# gsm_LoRa_due.net
KiCad netlist of a schematic drawn in EAGLE
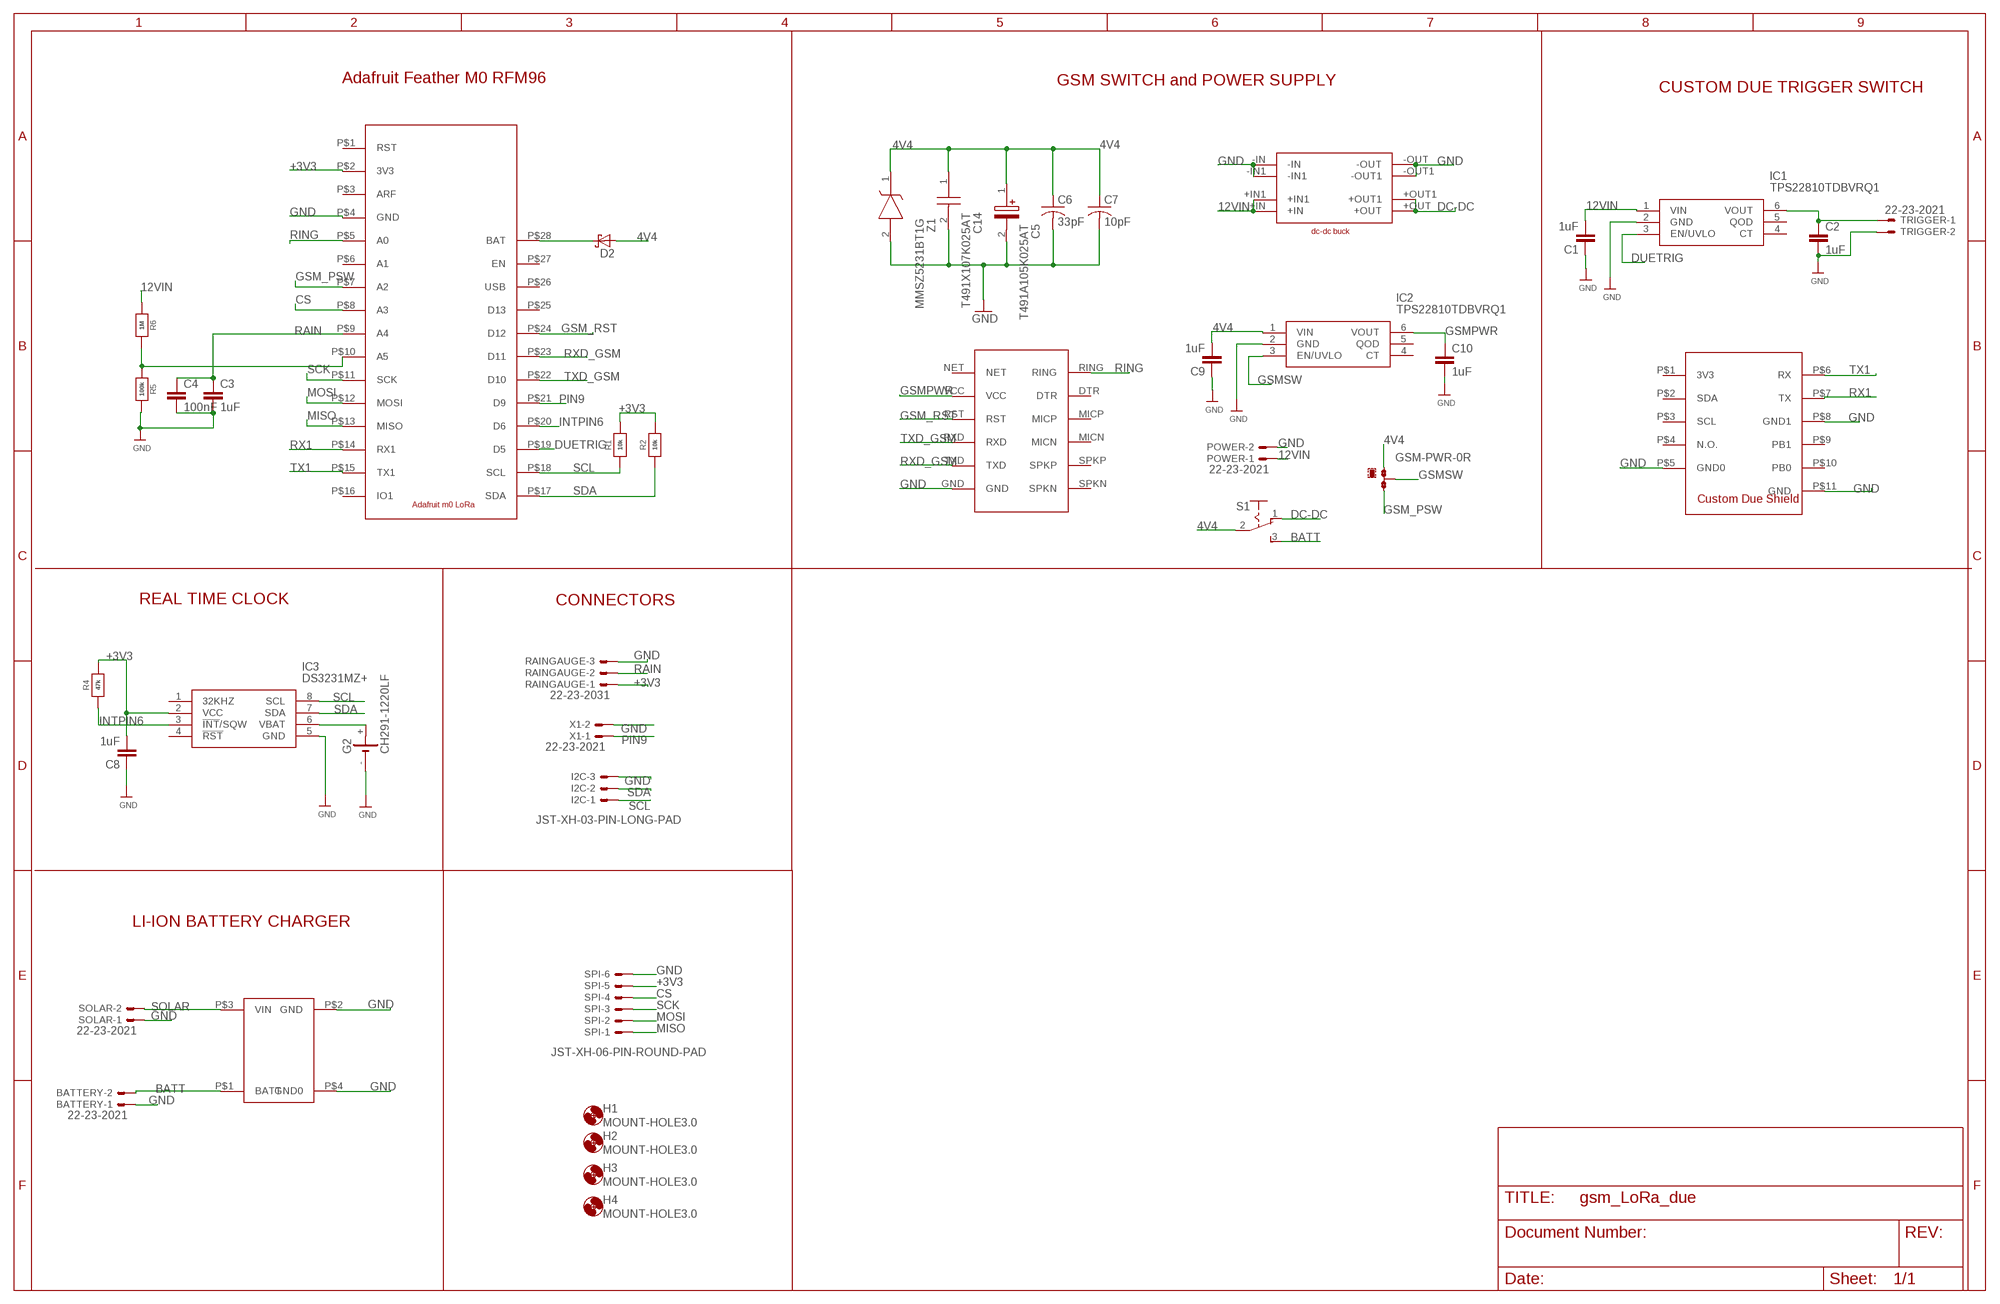
[diagram p0: schematic, sheet 1]

(export (version "E")
  (design (tool "Eeschema 10.0.6"))
  (components
    (comp (ref "BATTERY")
      (value "22-23-2021")
      (footprint "eagle-import:22-23-2021")
      (fields (field (name "MF") "MOLEX"))
      (libsource (lib "eagle-import") (part "22-23-2021"))
    )
    (comp (ref "C1")
      (value "1uF")
      (footprint "eagle-import:C0603")
      (libsource (lib "eagle-import") (part "CC0603"))
    )
    (comp (ref "C2")
      (value "1uF")
      (footprint "eagle-import:C0603")
      (libsource (lib "eagle-import") (part "CC0603"))
    )
    (comp (ref "C3")
      (value "1uF")
      (footprint "eagle-import:C0603")
      (libsource (lib "eagle-import") (part "CC0603"))
    )
    (comp (ref "C4")
      (value "100nF")
      (footprint "eagle-import:C0603")
      (libsource (lib "eagle-import") (part "CC0603"))
    )
    (comp (ref "C5")
      (value "T491A105K025AT")
      (footprint "eagle-import:CAPPM3216X180N")
      (fields (field (name "RS_PART_NUMBER") "8685769"))
      (libsource (lib "eagle-import") (part "T491A105K025AT"))
    )
    (comp (ref "C6")
      (value "33pF")
      (footprint "eagle-import:C0603")
      (libsource (lib "eagle-import") (part "C-USC0603"))
    )
    (comp (ref "C7")
      (value "10pF")
      (footprint "eagle-import:C0603")
      (libsource (lib "eagle-import") (part "C-USC0603"))
    )
    (comp (ref "C8")
      (value "1uF")
      (footprint "eagle-import:C0603")
      (libsource (lib "eagle-import") (part "CC0603"))
    )
    (comp (ref "C9")
      (value "1uF")
      (footprint "eagle-import:C0603")
      (libsource (lib "eagle-import") (part "CC0603"))
    )
    (comp (ref "C10")
      (value "1uF")
      (footprint "eagle-import:C0603")
      (libsource (lib "eagle-import") (part "CC0603"))
    )
    (comp (ref "C14")
      (value "T491X107K025AT")
      (footprint "eagle-import:CAPPM7343X430N")
      (fields (field (name "RS_PART_NUMBER") "8015511P"))
      (libsource (lib "eagle-import") (part "T491X107K025AT"))
    )
    (comp (ref "D2")
      (value "SCHOTTKY-DIODE")
      (footprint "eagle-import:DIODE_SMB")
      (libsource (lib "eagle-import") (part "SCHOTTKY-DIODE"))
    )
    (comp (ref "G2")
      (value "CH291-1220LF")
      (footprint "eagle-import:CH291-1220LF")
      (libsource (lib "eagle-import") (part "CH291-1220LF"))
    )
    (comp (ref "GSM-PWR")
      (value "0R-JUMPB")
      (footprint "eagle-import:B0R-JMP")
      (libsource (lib "eagle-import") (part "0R-JUMPB"))
    )
    (comp (ref "H1")
      (value "MOUNT-HOLE3.0")
      (footprint "eagle-import:3,0")
      (libsource (lib "eagle-import") (part "MOUNT-HOLE3.0"))
    )
    (comp (ref "H2")
      (value "MOUNT-HOLE3.0")
      (footprint "eagle-import:3,0")
      (libsource (lib "eagle-import") (part "MOUNT-HOLE3.0"))
    )
    (comp (ref "H3")
      (value "MOUNT-HOLE3.0")
      (footprint "eagle-import:3,0")
      (libsource (lib "eagle-import") (part "MOUNT-HOLE3.0"))
    )
    (comp (ref "H4")
      (value "MOUNT-HOLE3.0")
      (footprint "eagle-import:3,0")
      (libsource (lib "eagle-import") (part "MOUNT-HOLE3.0"))
    )
    (comp (ref "I2C")
      (value "JST-XH-03-PIN-LONG-PAD")
      (footprint "eagle-import:JST-XH-03-PACKAGE-LONG-PAD")
      (libsource (lib "eagle-import") (part "JST-XH-03-PIN-LONG-PAD"))
    )
    (comp (ref "IC1")
      (value "TPS22810TDBVRQ1")
      (footprint "eagle-import:SOT95P280X145-6N")
      (libsource (lib "eagle-import") (part "TPS22810TDBVRQ1"))
    )
    (comp (ref "IC2")
      (value "TPS22810TDBVRQ1")
      (footprint "eagle-import:SOT95P280X145-6N")
      (libsource (lib "eagle-import") (part "TPS22810TDBVRQ1"))
    )
    (comp (ref "IC3")
      (value "DS3231MZ+")
      (footprint "eagle-import:SOIC127P600X175-8N")
      (fields (field (name "RS_PART_NUMBER") "1897249"))
      (libsource (lib "eagle-import") (part "DS3231MZ+"))
    )
    (comp (ref "POWER")
      (value "22-23-2021")
      (footprint "eagle-import:22-23-2021")
      (fields (field (name "MF") "MOLEX"))
      (libsource (lib "eagle-import") (part "22-23-2021"))
    )
    (comp (ref "R1")
      (value "10k")
      (footprint "eagle-import:0603-NO")
      (libsource (lib "eagle-import") (part "RESISTOR_0603_NOOUT"))
    )
    (comp (ref "R2")
      (value "10k")
      (footprint "eagle-import:0603-NO")
      (libsource (lib "eagle-import") (part "RESISTOR_0603_NOOUT"))
    )
    (comp (ref "R4")
      (value "47k")
      (footprint "eagle-import:0603-NO")
      (libsource (lib "eagle-import") (part "RESISTOR_0603_NOOUT"))
    )
    (comp (ref "R5")
      (value "100k")
      (footprint "eagle-import:0603-NO")
      (libsource (lib "eagle-import") (part "RESISTOR_0603_NOOUT"))
    )
    (comp (ref "R6")
      (value "1M")
      (footprint "eagle-import:0603-NO")
      (libsource (lib "eagle-import") (part "RESISTOR_0603_NOOUT"))
    )
    (comp (ref "RAINGAUGE")
      (value "22-23-2031")
      (footprint "eagle-import:22-23-2031")
      (fields (field (name "MF") "MOLEX"))
      (libsource (lib "eagle-import") (part "22-23-2031"))
    )
    (comp (ref "S1")
      (value "255SB")
      (footprint "eagle-import:255SB")
      (libsource (lib "eagle-import") (part "255SB"))
    )
    (comp (ref "SOLAR")
      (value "22-23-2021")
      (footprint "eagle-import:22-23-2021")
      (fields (field (name "MF") "MOLEX"))
      (libsource (lib "eagle-import") (part "22-23-2021"))
    )
    (comp (ref "SPI")
      (value "JST-XH-06-PIN-ROUND-PAD")
      (footprint "eagle-import:JST-XH-06-PACKAGE-ROUND-PAD")
      (libsource (lib "eagle-import") (part "JST-XH-06-PIN-ROUND-PAD"))
    )
    (comp (ref "TRIGGER")
      (value "22-23-2021")
      (footprint "eagle-import:22-23-2021")
      (fields (field (name "MF") "MOLEX"))
      (libsource (lib "eagle-import") (part "22-23-2021"))
    )
    (comp (ref "U$1")
      (value "M0_LORA")
      (footprint "eagle-import:RFM69")
      (libsource (lib "eagle-import") (part "M0_LORA"))
    )
    (comp (ref "U$8")
      (value "DUE_PADSDUE_GSM")
      (footprint "eagle-import:DUESHIELD_BIG")
      (libsource (lib "eagle-import") (part "DUE_PADSDUE_GSM"))
    )
    (comp (ref "U$9")
      (value "SIM800L_MODULE")
      (footprint "eagle-import:SIM800L")
      (libsource (lib "eagle-import") (part "SIM800L_MODULE"))
    )
    (comp (ref "U$10")
      (value "DC-DC_BUCK_MAD")
      (footprint "eagle-import:DC-DC_BUCK")
      (libsource (lib "eagle-import") (part "DC-DC_BUCK_MAD"))
    )
    (comp (ref "U$11")
      (value "LI-ION-CHARGER")
      (footprint "eagle-import:LI-ION")
      (libsource (lib "eagle-import") (part "LI-ION-CHARGER"))
    )
    (comp (ref "X1")
      (value "22-23-2021")
      (footprint "eagle-import:22-23-2021")
      (fields (field (name "MF") "MOLEX"))
      (libsource (lib "eagle-import") (part "22-23-2021"))
    )
    (comp (ref "Z1")
      (value "MMSZ5231BT1G")
      (footprint "eagle-import:SOD3716X135N")
      (fields (field (name "RS_PART_NUMBER") "5453049P"))
      (libsource (lib "eagle-import") (part "MMSZ5231BT1G"))
    )
  )
  (nets
    (net (code "1") (name "/+3V3") (class "Default")
      (node (ref "C8") (pin "2") (pinfunction "2_2") (pintype "passive"))
      (node (ref "IC3") (pin "2") (pinfunction "VCC_2") (pintype "power_in"))
      (node (ref "R1") (pin "2") (pinfunction "2_2") (pintype "passive"))
      (node (ref "R2") (pin "2") (pinfunction "2_2") (pintype "passive"))
      (node (ref "R4") (pin "2") (pinfunction "2_2") (pintype "passive"))
      (node (ref "RAINGAUGE") (pin "1") (pinfunction "S_1") (pintype "passive"))
      (node (ref "SPI") (pin "5") (pinfunction "S_5") (pintype "passive"))
      (node (ref "U$1") (pin "P$2") (pinfunction "3V3_P$2") (pintype "bidirectional"))
    )
    (net (code "2") (name "/4V4") (class "Default")
      (node (ref "C14") (pin "1") (pinfunction "1_1") (pintype "bidirectional"))
      (node (ref "C5") (pin "1") (pinfunction "+_1") (pintype "bidirectional"))
      (node (ref "C6") (pin "1") (pinfunction "1_1") (pintype "passive"))
      (node (ref "C7") (pin "1") (pinfunction "1_1") (pintype "passive"))
      (node (ref "C9") (pin "2") (pinfunction "2_2") (pintype "passive"))
      (node (ref "D2") (pin "A") (pinfunction "C_A") (pintype "passive"))
      (node (ref "GSM-PWR") (pin "1") (pinfunction "1_1") (pintype "passive"))
      (node (ref "IC2") (pin "1") (pinfunction "VIN_1") (pintype "bidirectional"))
      (node (ref "S1") (pin "2") (pinfunction "P_2") (pintype "passive"))
      (node (ref "Z1") (pin "1") (pinfunction "K_1") (pintype "bidirectional"))
    )
    (net (code "3") (name "/12VIN") (class "Default")
      (node (ref "C1") (pin "2") (pinfunction "2_2") (pintype "passive"))
      (node (ref "IC1") (pin "1") (pinfunction "VIN_1") (pintype "bidirectional"))
      (node (ref "POWER") (pin "1") (pinfunction "S_1") (pintype "passive"))
      (node (ref "R6") (pin "1") (pinfunction "1_1") (pintype "passive"))
      (node (ref "U$10") (pin "+IN") (pinfunction "+IN_+IN") (pintype "bidirectional"))
      (node (ref "U$10") (pin "+IN1") (pinfunction "+IN1_+IN1") (pintype "bidirectional"))
    )
    (net (code "4") (name "/BATT") (class "Default")
      (node (ref "BATTERY") (pin "2") (pinfunction "S_2") (pintype "passive"))
      (node (ref "S1") (pin "3") (pinfunction "S_3") (pintype "passive"))
      (node (ref "U$11") (pin "P$1") (pinfunction "BATT_P$1") (pintype "bidirectional"))
    )
    (net (code "5") (name "/CS") (class "Default")
      (node (ref "SPI") (pin "4") (pinfunction "S_4") (pintype "passive"))
      (node (ref "U$1") (pin "P$8") (pinfunction "A3_P$8") (pintype "bidirectional"))
    )
    (net (code "6") (name "/DC-DC") (class "Default")
      (node (ref "S1") (pin "1") (pinfunction "O_1") (pintype "passive"))
      (node (ref "U$10") (pin "+OUT") (pinfunction "+OUT_+OUT") (pintype "bidirectional"))
      (node (ref "U$10") (pin "+OUT1") (pinfunction "+OUT1_+OUT1") (pintype "bidirectional"))
    )
    (net (code "7") (name "/DUETRIG") (class "Default")
      (node (ref "IC1") (pin "3") (pinfunction "EN/UVLO_3") (pintype "bidirectional"))
      (node (ref "U$1") (pin "P$19") (pinfunction "D5_P$19") (pintype "bidirectional"))
    )
    (net (code "8") (name "/GSMPWR") (class "Default")
      (node (ref "C10") (pin "1") (pinfunction "1_1") (pintype "passive"))
      (node (ref "IC2") (pin "6") (pinfunction "VOUT_6") (pintype "bidirectional"))
      (node (ref "U$9") (pin "VCC") (pinfunction "VCC_VCC") (pintype "bidirectional"))
    )
    (net (code "9") (name "/GSMSW") (class "Default")
      (node (ref "GSM-PWR") (pin "2") (pinfunction "2_2") (pintype "passive"))
      (node (ref "IC2") (pin "3") (pinfunction "EN/UVLO_3") (pintype "bidirectional"))
    )
    (net (code "10") (name "/GSM_PSW") (class "Default")
      (node (ref "GSM-PWR") (pin "3") (pinfunction "3_3") (pintype "passive"))
      (node (ref "U$1") (pin "P$7") (pinfunction "A2_P$7") (pintype "bidirectional"))
    )
    (net (code "11") (name "/GSM_RST") (class "Default")
      (node (ref "U$1") (pin "P$24") (pinfunction "D12_P$24") (pintype "bidirectional"))
      (node (ref "U$9") (pin "RST") (pinfunction "RST_RST") (pintype "bidirectional"))
    )
    (net (code "12") (name "/INTPIN6") (class "Default")
      (node (ref "IC3") (pin "3") (pinfunction "~{INT}/SQW_3") (pintype "input"))
      (node (ref "R4") (pin "1") (pinfunction "1_1") (pintype "passive"))
      (node (ref "U$1") (pin "P$20") (pinfunction "D6_P$20") (pintype "bidirectional"))
    )
    (net (code "13") (name "/MISO") (class "Default")
      (node (ref "SPI") (pin "1") (pinfunction "S_1") (pintype "passive"))
      (node (ref "U$1") (pin "P$13") (pinfunction "MISO_P$13") (pintype "bidirectional"))
    )
    (net (code "14") (name "/MOSI") (class "Default")
      (node (ref "SPI") (pin "2") (pinfunction "S_2") (pintype "passive"))
      (node (ref "U$1") (pin "P$12") (pinfunction "MOSI_P$12") (pintype "bidirectional"))
    )
    (net (code "15") (name "/PIN9") (class "Default")
      (node (ref "U$1") (pin "P$21") (pinfunction "D9_P$21") (pintype "bidirectional"))
      (node (ref "X1") (pin "1") (pinfunction "S_1") (pintype "passive"))
    )
    (net (code "16") (name "/RAIN") (class "Default")
      (node (ref "C3") (pin "1") (pinfunction "1_1") (pintype "passive"))
      (node (ref "C4") (pin "1") (pinfunction "1_1") (pintype "passive"))
      (node (ref "RAINGAUGE") (pin "2") (pinfunction "S_2") (pintype "passive"))
      (node (ref "U$1") (pin "P$9") (pinfunction "A4_P$9") (pintype "bidirectional"))
    )
    (net (code "17") (name "/RING") (class "Default")
      (node (ref "U$1") (pin "P$5") (pinfunction "A0_P$5") (pintype "bidirectional"))
      (node (ref "U$9") (pin "RING") (pinfunction "RING_RING") (pintype "bidirectional"))
    )
    (net (code "18") (name "/RX1") (class "Default")
      (node (ref "U$1") (pin "P$14") (pinfunction "RX1_P$14") (pintype "bidirectional"))
      (node (ref "U$8") (pin "P$7") (pinfunction "TX_P$7") (pintype "bidirectional"))
    )
    (net (code "19") (name "/RXD_GSM") (class "Default")
      (node (ref "U$1") (pin "P$23") (pinfunction "D11_P$23") (pintype "bidirectional"))
      (node (ref "U$9") (pin "TXD") (pinfunction "TXD_TXD") (pintype "bidirectional"))
    )
    (net (code "20") (name "/SCK") (class "Default")
      (node (ref "SPI") (pin "3") (pinfunction "S_3") (pintype "passive"))
      (node (ref "U$1") (pin "P$11") (pinfunction "SCK_P$11") (pintype "bidirectional"))
    )
    (net (code "21") (name "/SCL") (class "Default")
      (node (ref "I2C") (pin "1") (pinfunction "S_1") (pintype "passive"))
      (node (ref "IC3") (pin "8") (pinfunction "SCL_8") (pintype "bidirectional"))
      (node (ref "R1") (pin "1") (pinfunction "1_1") (pintype "passive"))
      (node (ref "U$1") (pin "P$18") (pinfunction "SCL_P$18") (pintype "bidirectional"))
    )
    (net (code "22") (name "/SDA") (class "Default")
      (node (ref "I2C") (pin "2") (pinfunction "S_2") (pintype "passive"))
      (node (ref "IC3") (pin "7") (pinfunction "SDA_7") (pintype "bidirectional"))
      (node (ref "R2") (pin "1") (pinfunction "1_1") (pintype "passive"))
      (node (ref "U$1") (pin "P$17") (pinfunction "SDA_P$17") (pintype "bidirectional"))
    )
    (net (code "23") (name "/SOLAR") (class "Default")
      (node (ref "SOLAR") (pin "2") (pinfunction "S_2") (pintype "passive"))
      (node (ref "U$11") (pin "P$3") (pinfunction "VIN_P$3") (pintype "bidirectional"))
    )
    (net (code "24") (name "/TX1") (class "Default")
      (node (ref "U$1") (pin "P$15") (pinfunction "TX1_P$15") (pintype "bidirectional"))
      (node (ref "U$8") (pin "P$6") (pinfunction "RX_P$6") (pintype "bidirectional"))
    )
    (net (code "25") (name "/TXD_GSM") (class "Default")
      (node (ref "U$1") (pin "P$22") (pinfunction "D10_P$22") (pintype "bidirectional"))
      (node (ref "U$9") (pin "RXD") (pinfunction "RXD_RXD") (pintype "bidirectional"))
    )
    (net (code "26") (name "GND") (class "Default")
      (node (ref "BATTERY") (pin "1") (pinfunction "S_1") (pintype "passive"))
      (node (ref "C1") (pin "1") (pinfunction "1_1") (pintype "passive"))
      (node (ref "C10") (pin "2") (pinfunction "2_2") (pintype "passive"))
      (node (ref "C14") (pin "2") (pinfunction "2_2") (pintype "bidirectional"))
      (node (ref "C2") (pin "2") (pinfunction "2_2") (pintype "passive"))
      (node (ref "C3") (pin "2") (pinfunction "2_2") (pintype "passive"))
      (node (ref "C4") (pin "2") (pinfunction "2_2") (pintype "passive"))
      (node (ref "C5") (pin "2") (pinfunction "-_2") (pintype "bidirectional"))
      (node (ref "C6") (pin "2") (pinfunction "2_2") (pintype "passive"))
      (node (ref "C7") (pin "2") (pinfunction "2_2") (pintype "passive"))
      (node (ref "C8") (pin "1") (pinfunction "1_1") (pintype "passive"))
      (node (ref "C9") (pin "1") (pinfunction "1_1") (pintype "passive"))
      (node (ref "G2") (pin "-") (pinfunction "-_-") (pintype "passive"))
      (node (ref "I2C") (pin "3") (pinfunction "S_3") (pintype "passive"))
      (node (ref "IC1") (pin "2") (pinfunction "GND_2") (pintype "bidirectional"))
      (node (ref "IC2") (pin "2") (pinfunction "GND_2") (pintype "bidirectional"))
      (node (ref "IC3") (pin "5") (pinfunction "GND_5") (pintype "power_in"))
      (node (ref "POWER") (pin "2") (pinfunction "S_2") (pintype "passive"))
      (node (ref "R5") (pin "2") (pinfunction "2_2") (pintype "passive"))
      (node (ref "RAINGAUGE") (pin "3") (pinfunction "S_3") (pintype "passive"))
      (node (ref "SOLAR") (pin "1") (pinfunction "S_1") (pintype "passive"))
      (node (ref "SPI") (pin "6") (pinfunction "S_6") (pintype "passive"))
      (node (ref "TRIGGER") (pin "2") (pinfunction "S_2") (pintype "passive"))
      (node (ref "U$1") (pin "P$4") (pinfunction "GND_P$4") (pintype "bidirectional"))
      (node (ref "U$10") (pin "-IN") (pinfunction "-IN_-IN") (pintype "bidirectional"))
      (node (ref "U$10") (pin "-IN1") (pinfunction "-IN1_-IN1") (pintype "bidirectional"))
      (node (ref "U$10") (pin "-OUT") (pinfunction "-OUT_-OUT") (pintype "bidirectional"))
      (node (ref "U$10") (pin "-OUT1") (pinfunction "-OUT1_-OUT1") (pintype "bidirectional"))
      (node (ref "U$11") (pin "P$2") (pinfunction "GND_P$2") (pintype "bidirectional"))
      (node (ref "U$11") (pin "P$4") (pinfunction "GND0_P$4") (pintype "bidirectional"))
      (node (ref "U$8") (pin "P$11") (pinfunction "GND_P$11") (pintype "bidirectional"))
      (node (ref "U$8") (pin "P$5") (pinfunction "GND0_P$5") (pintype "bidirectional"))
      (node (ref "U$8") (pin "P$8") (pinfunction "GND1_P$8") (pintype "bidirectional"))
      (node (ref "U$9") (pin "GND") (pinfunction "GND_GND") (pintype "bidirectional"))
      (node (ref "X1") (pin "2") (pinfunction "S_2") (pintype "passive"))
      (node (ref "Z1") (pin "2") (pinfunction "A_2") (pintype "bidirectional"))
    )
    (net (code "27") (name "Net-(D2-A)") (class "Default")
      (node (ref "D2") (pin "C") (pinfunction "A_C") (pintype "passive"))
      (node (ref "U$1") (pin "P$28") (pinfunction "BAT_P$28") (pintype "bidirectional"))
    )
    (net (code "28") (name "Net-(IC1-VOUT)") (class "Default")
      (node (ref "C2") (pin "1") (pinfunction "1_1") (pintype "passive"))
      (node (ref "IC1") (pin "6") (pinfunction "VOUT_6") (pintype "bidirectional"))
      (node (ref "TRIGGER") (pin "1") (pinfunction "S_1") (pintype "passive"))
    )
    (net (code "29") (name "Net-(IC3-VBAT)") (class "Default")
      (node (ref "G2") (pin "+") (pinfunction "+_+") (pintype "passive"))
      (node (ref "IC3") (pin "6") (pinfunction "VBAT_6") (pintype "bidirectional"))
    )
    (net (code "30") (name "Net-(U$1-A5)") (class "Default")
      (node (ref "R5") (pin "1") (pinfunction "1_1") (pintype "passive"))
      (node (ref "R6") (pin "2") (pinfunction "2_2") (pintype "passive"))
      (node (ref "U$1") (pin "P$10") (pinfunction "A5_P$10") (pintype "bidirectional"))
    )
    (net (code "31") (name "unconnected-(IC1-CT-Pad4)") (class "Default")
      (node (ref "IC1") (pin "4") (pinfunction "CT_4") (pintype "bidirectional"))
    )
    (net (code "32") (name "unconnected-(IC1-QOD-Pad5)") (class "Default")
      (node (ref "IC1") (pin "5") (pinfunction "QOD_5") (pintype "bidirectional"))
    )
    (net (code "33") (name "unconnected-(IC2-CT-Pad4)") (class "Default")
      (node (ref "IC2") (pin "4") (pinfunction "CT_4") (pintype "bidirectional"))
    )
    (net (code "34") (name "unconnected-(IC2-QOD-Pad5)") (class "Default")
      (node (ref "IC2") (pin "5") (pinfunction "QOD_5") (pintype "bidirectional"))
    )
    (net (code "35") (name "unconnected-(IC3-32KHZ-Pad1)") (class "Default")
      (node (ref "IC3") (pin "1") (pinfunction "32KHZ_1") (pintype "bidirectional"))
    )
    (net (code "36") (name "unconnected-(IC3-~{RST}-Pad4)") (class "Default")
      (node (ref "IC3") (pin "4") (pinfunction "~{RST}_4") (pintype "input"))
    )
    (net (code "37") (name "unconnected-(U$1-A1-PadP$6)") (class "Default")
      (node (ref "U$1") (pin "P$6") (pinfunction "A1_P$6") (pintype "bidirectional"))
    )
    (net (code "38") (name "unconnected-(U$1-ARF-PadP$3)") (class "Default")
      (node (ref "U$1") (pin "P$3") (pinfunction "ARF_P$3") (pintype "bidirectional"))
    )
    (net (code "39") (name "unconnected-(U$1-D13-PadP$25)") (class "Default")
      (node (ref "U$1") (pin "P$25") (pinfunction "D13_P$25") (pintype "bidirectional"))
    )
    (net (code "40") (name "unconnected-(U$1-EN-PadP$27)") (class "Default")
      (node (ref "U$1") (pin "P$27") (pinfunction "EN_P$27") (pintype "bidirectional"))
    )
    (net (code "41") (name "unconnected-(U$1-IO1-PadP$16)") (class "Default")
      (node (ref "U$1") (pin "P$16") (pinfunction "IO1_P$16") (pintype "bidirectional"))
    )
    (net (code "42") (name "unconnected-(U$1-RST-PadP$1)") (class "Default")
      (node (ref "U$1") (pin "P$1") (pinfunction "RST_P$1") (pintype "bidirectional"))
    )
    (net (code "43") (name "unconnected-(U$1-USB-PadP$26)") (class "Default")
      (node (ref "U$1") (pin "P$26") (pinfunction "USB_P$26") (pintype "bidirectional"))
    )
    (net (code "44") (name "unconnected-(U$8-3V3-PadP$1)") (class "Default")
      (node (ref "U$8") (pin "P$1") (pinfunction "3V3_P$1") (pintype "bidirectional"))
    )
    (net (code "45") (name "unconnected-(U$8-N.O.-PadP$4)") (class "Default")
      (node (ref "U$8") (pin "P$4") (pinfunction "N.O._P$4") (pintype "bidirectional"))
    )
    (net (code "46") (name "unconnected-(U$8-PB0-PadP$10)") (class "Default")
      (node (ref "U$8") (pin "P$10") (pinfunction "PB0_P$10") (pintype "bidirectional"))
    )
    (net (code "47") (name "unconnected-(U$8-PB1-PadP$9)") (class "Default")
      (node (ref "U$8") (pin "P$9") (pinfunction "PB1_P$9") (pintype "bidirectional"))
    )
    (net (code "48") (name "unconnected-(U$8-SCL-PadP$3)") (class "Default")
      (node (ref "U$8") (pin "P$3") (pinfunction "SCL_P$3") (pintype "bidirectional"))
    )
    (net (code "49") (name "unconnected-(U$8-SDA-PadP$2)") (class "Default")
      (node (ref "U$8") (pin "P$2") (pinfunction "SDA_P$2") (pintype "bidirectional"))
    )
    (net (code "50") (name "unconnected-(U$9-PadDTR)") (class "Default")
      (node (ref "U$9") (pin "DTR") (pinfunction "DTR_DTR") (pintype "bidirectional"))
    )
    (net (code "51") (name "unconnected-(U$9-PadMICN)") (class "Default")
      (node (ref "U$9") (pin "MICN") (pinfunction "MICN_MICN") (pintype "bidirectional"))
    )
    (net (code "52") (name "unconnected-(U$9-PadMICP)") (class "Default")
      (node (ref "U$9") (pin "MICP") (pinfunction "MICP_MICP") (pintype "bidirectional"))
    )
    (net (code "53") (name "unconnected-(U$9-PadNET)") (class "Default")
      (node (ref "U$9") (pin "NET") (pinfunction "NET_NET") (pintype "bidirectional"))
    )
    (net (code "54") (name "unconnected-(U$9-PadSPKN)") (class "Default")
      (node (ref "U$9") (pin "SPKN") (pinfunction "SPKN_SPKN") (pintype "bidirectional"))
    )
    (net (code "55") (name "unconnected-(U$9-PadSPKP)") (class "Default")
      (node (ref "U$9") (pin "SPKP") (pinfunction "SPKP_SPKP") (pintype "bidirectional"))
    )
  )
)
